# MIXR_Power_-_Battery_Management_System.net
KiCad netlist of a schematic drawn in Altium Designer
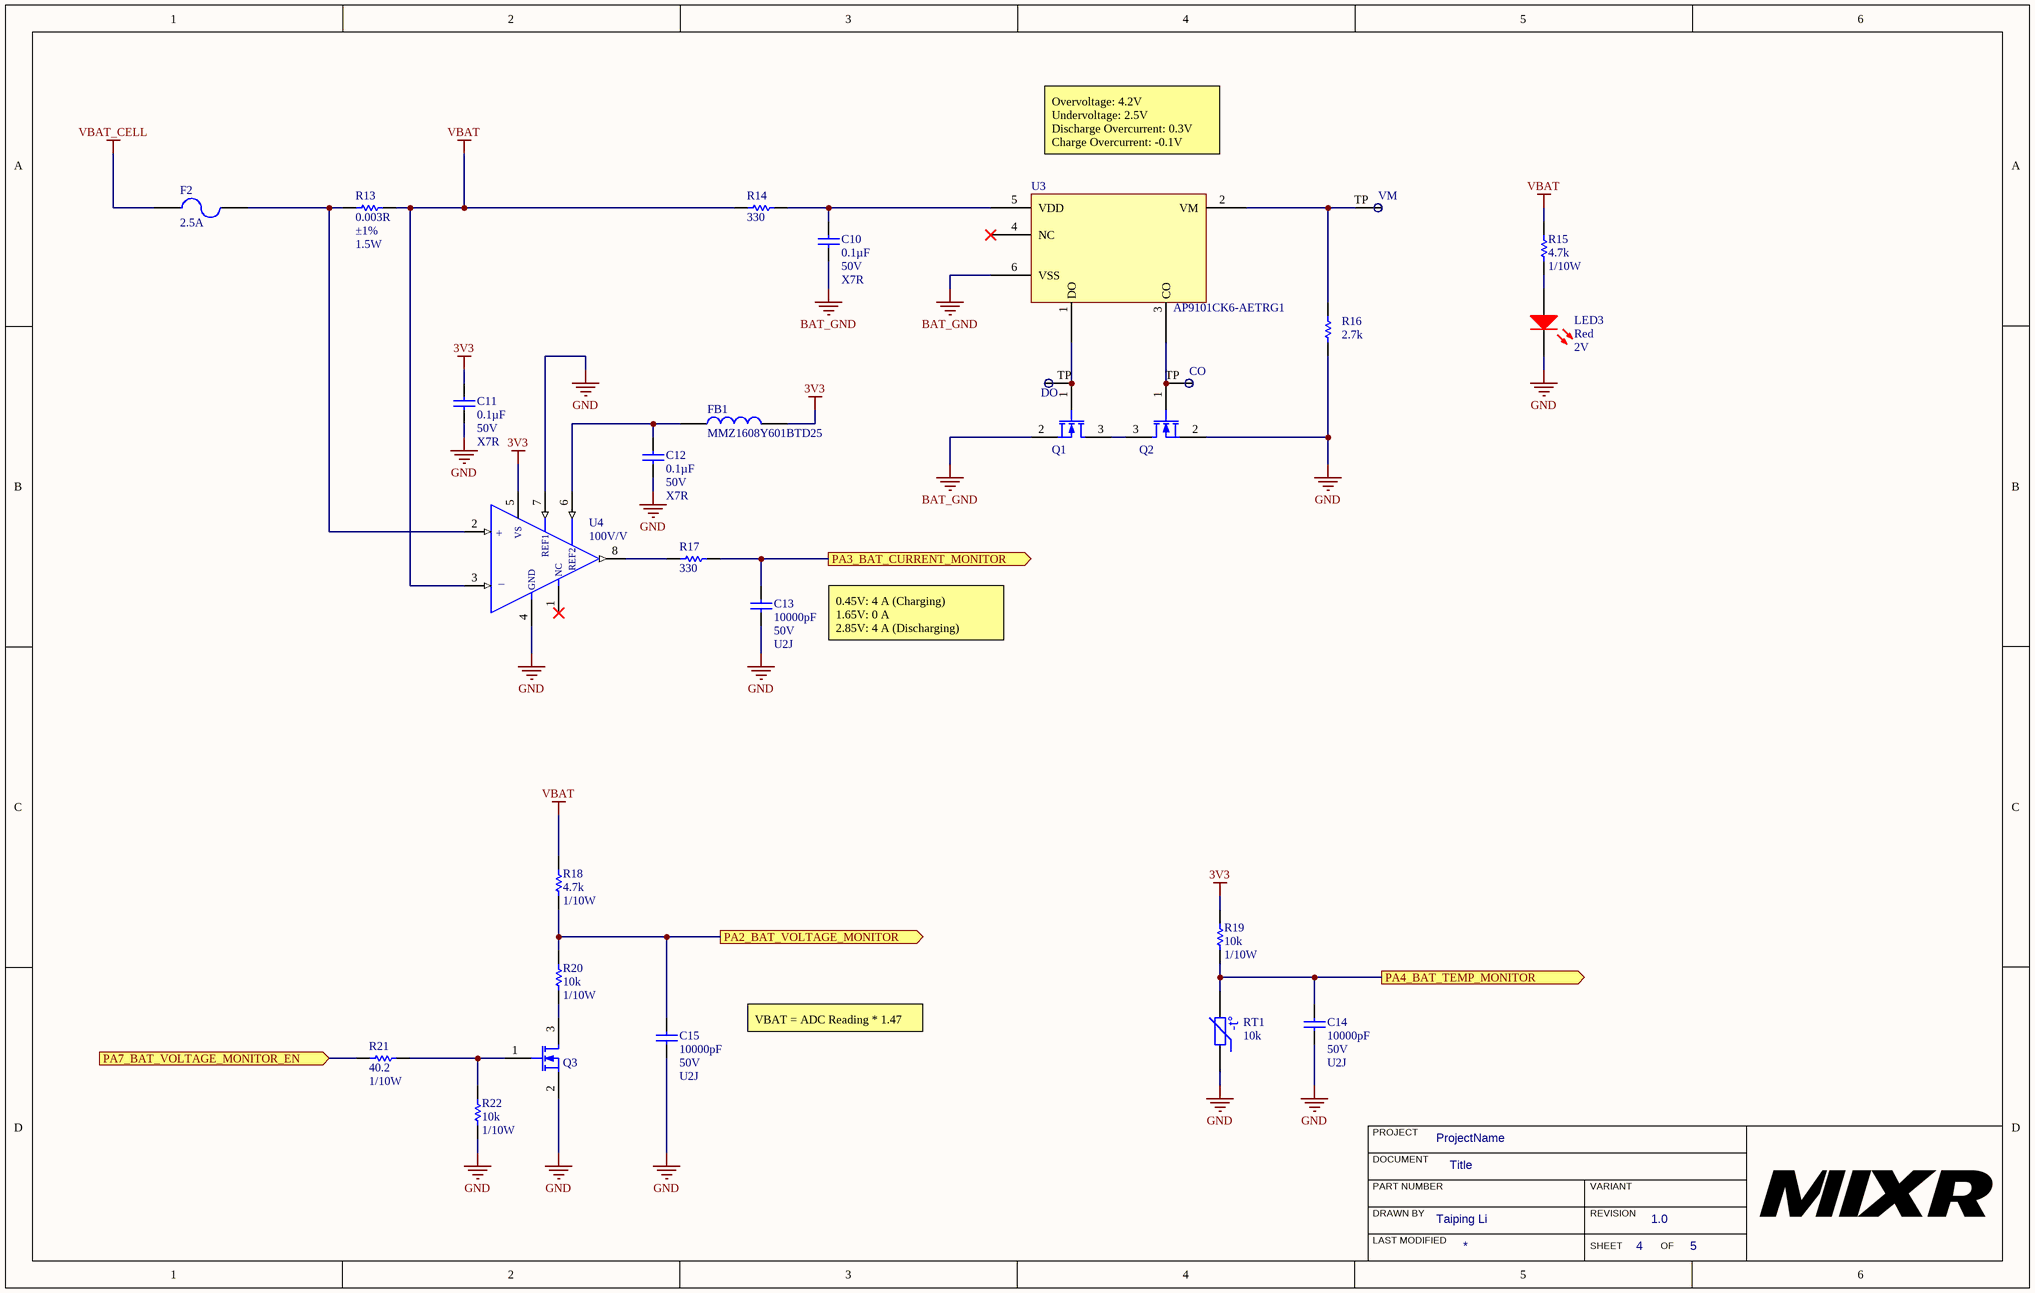
[diagram p0: MIXR Power - Battery Management System.SchDoc]

(export (version "E")
  (design (tool "Eeschema 10.0.6"))
  (components
    (comp (ref "C10")
      (value "CAP CER 0.1UF 50V 10% X7R 0603")
      (footprint "CAP, 0603")
      (description "0.10µF ±10% 50V Ceramic Capacitor X7R 0603 (1608 Metric)")
      (fields
        (field (name "TOLERANCE") "±10%")
        (field (name "CAPACITANCE") "0.1µF")
        (field (name "VOLTAGE") "50V")
        (field (name "TEMPERATURE COEFFICIENT") "X7R")
      )
      (libsource (lib "Schematic Diagrams") (part "CAP CER 0.1UF 50V 10% X7R 0603"))
    )
    (comp (ref "C11")
      (value "CAP CER 0.1UF 50V 10% X7R 0603")
      (footprint "CAP, 0603")
      (description "0.10µF ±10% 50V Ceramic Capacitor X7R 0603 (1608 Metric)")
      (fields
        (field (name "TOLERANCE") "±10%")
        (field (name "CAPACITANCE") "0.1µF")
        (field (name "VOLTAGE") "50V")
        (field (name "TEMPERATURE COEFFICIENT") "X7R")
      )
      (libsource (lib "Schematic Diagrams") (part "CAP CER 0.1UF 50V 10% X7R 0603"))
    )
    (comp (ref "C12")
      (value "CAP CER 0.1UF 50V 10% X7R 0603")
      (footprint "CAP, 0603")
      (description "0.10µF ±10% 50V Ceramic Capacitor X7R 0603 (1608 Metric)")
      (fields
        (field (name "TOLERANCE") "±10%")
        (field (name "CAPACITANCE") "0.1µF")
        (field (name "VOLTAGE") "50V")
        (field (name "TEMPERATURE COEFFICIENT") "X7R")
      )
      (libsource (lib "Schematic Diagrams") (part "CAP CER 0.1UF 50V 10% X7R 0603"))
    )
    (comp (ref "C13")
      (value "CAP CER 10nF 50V 5% X7R 0603")
      (footprint "CAP, 0603")
      (description "10000pF ±5% 50V Ceramic Capacitor U2J 0603 (1608 Metric)")
      (fields
        (field (name "TOLERANCE") "±5%")
        (field (name "CAPACITANCE") "10000pF")
        (field (name "VOLTAGE") "50V")
        (field (name "TEMPERATURE COEFFICIENT") "U2J")
      )
      (libsource (lib "Schematic Diagrams") (part "CAP CER 10nF 50V 5% X7R 0603"))
    )
    (comp (ref "C14")
      (value "CAP CER 10nF 50V 5% X7R 0603")
      (footprint "CAP, 0603")
      (description "10000pF ±5% 50V Ceramic Capacitor U2J 0603 (1608 Metric)")
      (fields
        (field (name "TOLERANCE") "±5%")
        (field (name "CAPACITANCE") "10000pF")
        (field (name "VOLTAGE") "50V")
        (field (name "TEMPERATURE COEFFICIENT") "U2J")
      )
      (libsource (lib "Schematic Diagrams") (part "CAP CER 10nF 50V 5% X7R 0603"))
    )
    (comp (ref "C15")
      (value "CAP CER 10nF 50V 5% X7R 0603")
      (footprint "CAP, 0603")
      (description "10000pF ±5% 50V Ceramic Capacitor U2J 0603 (1608 Metric)")
      (fields
        (field (name "TOLERANCE") "±5%")
        (field (name "CAPACITANCE") "10000pF")
        (field (name "VOLTAGE") "50V")
        (field (name "TEMPERATURE COEFFICIENT") "U2J")
      )
      (libsource (lib "Schematic Diagrams") (part "CAP CER 10nF 50V 5% X7R 0603"))
    )
    (comp (ref "CO")
      (value "Test Point")
      (footprint "Test Point")
      (libsource (lib "Schematic Diagrams") (part "Test Point"))
    )
    (comp (ref "DO")
      (value "Test Point")
      (footprint "Test Point")
      (libsource (lib "Schematic Diagrams") (part "Test Point"))
    )
    (comp (ref "F2")
      (value "FUSE 2.5A 32VDC 1206")
      (footprint "FUSE LITTLEFUSE 0466 1206")
      (description "2.5A 32V AC 32V DC Fuse Board Mount (Cartridge Style Excluded) Surface Mount 1206 (3216 Metric)")
      (fields (field (name "CURRENT RATING") "2.5A"))
      (libsource (lib "Schematic Diagrams") (part "FUSE 2.5A 32VDC 1206"))
    )
    (comp (ref "FB1")
      (value "FB 600 OHM 1LN 0603")
      (footprint "FB 0603")
      (description "FERRITE BEAD 600 OHM 0603 1LN")
      (fields
        (field (name "MANUFACTURER") "TDK")
        (field (name "TOLERANCE") "25%")
        (field (name "MANUFACTURER PART NUMBER") "MMZ1608Y601BTD25")
      )
      (libsource (lib "Schematic Diagrams") (part "FB 600 OHM 1LN 0603"))
    )
    (comp (ref "LED3")
      (value "LED RED CLEAR 2V 0603")
      (footprint "LED_0603")
      (description "Red 631nm LED Indication - Discrete 2V 0603 (1608 Metric)")
      (fields
        (field (name "MANUFACTURER") "Wurth Electronics Inc.")
        (field (name "MANUFACTURER PART NUMBER") "150060RS75000")
        (field (name "COLOR") "Red")
        (field (name "VOLTAGE - FORWARD (VF) (TYP)") "2V")
      )
      (libsource (lib "Schematic Diagrams") (part "LED RED CLEAR 2V 0603"))
    )
    (comp (ref "Q1")
      (value "MOSFET N-CH 30V 6.2A 0.9W SOT-23")
      (footprint "MOSFET N-CH 30V 6.2A 0.9W SOT-23")
      (description "N-Channel 30V 6.2A (Ta) 900mW (Ta) Surface Mount SOT-23")
      (fields (field (name "MANUFACTURER") "Diodes") (field (name "MANUFACTURER PART NUMBER") "DMN3023L-7"))
      (libsource (lib "Schematic Diagrams") (part "MOSFET N-CH 30V 6.2A 0.9W SOT-23"))
    )
    (comp (ref "Q2")
      (value "MOSFET N-CH 30V 6.2A 0.9W SOT-23")
      (footprint "MOSFET N-CH 30V 6.2A 0.9W SOT-23")
      (description "N-Channel 30V 6.2A (Ta) 900mW (Ta) Surface Mount SOT-23")
      (fields (field (name "MANUFACTURER") "Diodes") (field (name "MANUFACTURER PART NUMBER") "DMN3023L-7"))
      (libsource (lib "Schematic Diagrams") (part "MOSFET N-CH 30V 6.2A 0.9W SOT-23"))
    )
    (comp (ref "Q3")
      (value "MOSFET N-CH 30V 6.2A 0.9W SOT-23")
      (footprint "MOSFET N-CH 30V 6.2A 0.9W SOT-23")
      (description "N-Channel 30V 6.2A (Ta) 900mW (Ta) Surface Mount SOT-23")
      (fields (field (name "MANUFACTURER") "Diodes") (field (name "MANUFACTURER PART NUMBER") "DMN3023L-7"))
      (libsource (lib "Schematic Diagrams") (part "MOSFET N-CH 30V 6.2A 0.9W SOT-23"))
    )
    (comp (ref "R13")
      (value "RES 0.003 OHM 1% 1.5W 2010")
      (footprint "RES 2010")
      (description "0.003 Ohm ±1% 1.5W Chip Resistor 2010 (5025 Metric) Current Sense, Moisture Resistant Metal Foil")
      (fields
        (field (name "RESISTANCE (OHMS)") "0.003R")
        (field (name "TOLERANCE") "±1%")
        (field (name "POWER (WATTS)") "1.5W")
      )
      (libsource (lib "Schematic Diagrams") (part "RES 0.003 OHM 1% 1.5W 2010"))
    )
    (comp (ref "R14")
      (value "330")
      (footprint "RES, 0603")
      (fields
        (field (name "MANUFACTURER") "TE Connectivity")
        (field (name "MANUFACTURER PART NUMBER") "CRGCQ0603F330R")
        (field (name "Comment") "RES 330 OHM 1% 1/10W 0603")
      )
      (libsource (lib "Schematic Diagrams") (part "RES 330 OHM 1% 1/10W 0603"))
    )
    (comp (ref "R15")
      (value "RES 4.7K OHM 1% 1/10W 0603")
      (footprint "RES, 0603")
      (description "4.7k Ohm ±1% 0.1W, 1/10W Chip Resistor 0603 (1608 Metric) Moisture Resistant Thick Film")
      (fields
        (field (name "TOLERANCE") "±1%")
        (field (name "RESISTANCE (OHMS)") "4.7k")
        (field (name "POWER (WATTS)") "1/10W")
      )
      (libsource (lib "Schematic Diagrams") (part "RES 4.7K OHM 1% 1/10W 0603"))
    )
    (comp (ref "R16")
      (value "2.7k")
      (footprint "RES, 0603")
      (fields
        (field (name "MANUFACTURER") "TE Connectivity")
        (field (name "MANUFACTURER PART NUMBER") "CRGCQ0603F2K7")
      )
      (libsource (lib "Schematic Diagrams") (part "RES 2.7K OHM 1% 1/10W 0603"))
    )
    (comp (ref "R17")
      (value "330")
      (footprint "RES, 0603")
      (fields
        (field (name "MANUFACTURER") "TE Connectivity")
        (field (name "MANUFACTURER PART NUMBER") "CRGCQ0603F330R")
        (field (name "Comment") "RES 330 OHM 1% 1/10W 0603")
      )
      (libsource (lib "Schematic Diagrams") (part "RES 330 OHM 1% 1/10W 0603"))
    )
    (comp (ref "R18")
      (value "RES 4.7K OHM 1% 1/10W 0603")
      (footprint "RES, 0603")
      (description "4.7k Ohm ±1% 0.1W, 1/10W Chip Resistor 0603 (1608 Metric) Moisture Resistant Thick Film")
      (fields
        (field (name "TOLERANCE") "±1%")
        (field (name "RESISTANCE (OHMS)") "4.7k")
        (field (name "POWER (WATTS)") "1/10W")
      )
      (libsource (lib "Schematic Diagrams") (part "RES 4.7K OHM 1% 1/10W 0603"))
    )
    (comp (ref "R19")
      (value "RES 10K OHM 1% 1/10W 0603")
      (footprint "RES, 0603")
      (description "RES SMD 10K OHM 1% 1/10W 0603")
      (fields
        (field (name "TOLERANCE") "±1%")
        (field (name "RESISTANCE") "10k")
        (field (name "POWER") "1/10W")
      )
      (libsource (lib "Schematic Diagrams") (part "RES 10K OHM 1% 1/10W 0603"))
    )
    (comp (ref "R20")
      (value "RES 10K OHM 1% 1/10W 0603")
      (footprint "RES, 0603")
      (description "RES SMD 10K OHM 1% 1/10W 0603")
      (fields
        (field (name "TOLERANCE") "±1%")
        (field (name "RESISTANCE") "10k")
        (field (name "POWER") "1/10W")
      )
      (libsource (lib "Schematic Diagrams") (part "RES 10K OHM 1% 1/10W 0603"))
    )
    (comp (ref "R21")
      (value "RES 40.2 OHM 0.5% 1/10W 0603")
      (footprint "RES, 0603")
      (description "RES SMD 40.2 OHM 0.5% 1/10W 0603")
      (fields
        (field (name "TOLERANCE") "±0.5%")
        (field (name "RESISTANCE") "40.2")
        (field (name "POWER") "1/10W")
      )
      (libsource (lib "Schematic Diagrams") (part "RES 40.2 OHM 0.5% 1/10W 0603"))
    )
    (comp (ref "R22")
      (value "RES 10K OHM 1% 1/10W 0603")
      (footprint "RES, 0603")
      (description "RES SMD 10K OHM 1% 1/10W 0603")
      (fields
        (field (name "TOLERANCE") "±1%")
        (field (name "RESISTANCE") "10k")
        (field (name "POWER") "1/10W")
      )
      (libsource (lib "Schematic Diagrams") (part "RES 10K OHM 1% 1/10W 0603"))
    )
    (comp (ref "RT1")
      (value "NTC THERMISTORS 10K 0603 SMD")
      (footprint "RES, 0603")
      (description "NTC THERMISTORS 10KOHM 1608 SMD")
      (fields
        (field (name "MANUFACTURER") "Murata Electronics North America")
        (field (name "MANUFACTURER PART NUMBER") "NCU18XH103F60RB")
        (field (name "RESISTANCE IN OHMS @ 25°C") "10k")
      )
      (libsource (lib "Schematic Diagrams") (part "NTC THERMISTORS 10K 0603 SMD"))
    )
    (comp (ref "U3")
      (value "IC BATT PROT LI-ION 1-CELL SOT26")
      (footprint "SOT23-6")
      (description "Battery Battery Protection IC Lithium Ion/Polymer SOT-26")
      (fields
        (field (name "MANUFACTURER") "Diodes")
        (field (name "MANUFACTURER PART NUMBER") "AP9101CK6-AETRG1")
      )
      (libsource (lib "Schematic Diagrams") (part "IC BATT PROT LI-ION 1-CELL SOT26"))
    )
    (comp (ref "U4")
      (value "100V/V")
      (footprint "IC CURRENT AMPLIFIER INA240 TSSOP-8")
      (description "Current Sense Amplifier 1 Circuit 8-TSSOP")
      (libsource (lib "Schematic Diagrams") (part "IC CURRENT AMPLIFIER INA240 8-TSSOP"))
    )
    (comp (ref "VM")
      (value "Test Point")
      (footprint "Test Point")
      (libsource (lib "Schematic Diagrams") (part "Test Point"))
    )
  )
  (nets
    (net (code "1") (name "/PA2_BAT_VOLTAGE_MONITOR") (class "Default")
      (node (ref "C15") (pin "1") (pinfunction "1_1") (pintype "passive"))
      (node (ref "R18") (pin "2") (pinfunction "2_2") (pintype "passive"))
      (node (ref "R20") (pin "1") (pinfunction "1_1") (pintype "passive"))
    )
    (net (code "2") (name "/PA3_BAT_CURRENT_MONITOR") (class "Default")
      (node (ref "C13") (pin "1") (pinfunction "1_1") (pintype "passive"))
      (node (ref "R17") (pin "2") (pinfunction "2_2") (pintype "passive"))
    )
    (net (code "3") (name "/PA4_BAT_TEMP_MONITOR") (class "Default")
      (node (ref "C14") (pin "1") (pinfunction "1_1") (pintype "passive"))
      (node (ref "R19") (pin "2") (pinfunction "2_2") (pintype "passive"))
      (node (ref "RT1") (pin "2") (pinfunction "2_2") (pintype "passive"))
    )
    (net (code "4") (name "/PA7_BAT_VOLTAGE_MONITOR_EN") (class "Default")
      (node (ref "R21") (pin "1") (pinfunction "1_1") (pintype "passive"))
    )
    (net (code "5") (name "3V3") (class "Default")
      (node (ref "C11") (pin "1") (pinfunction "1_1") (pintype "passive"))
      (node (ref "FB1") (pin "2") (pinfunction "2_2") (pintype "passive"))
      (node (ref "R19") (pin "1") (pinfunction "1_1") (pintype "passive"))
      (node (ref "U4") (pin "5") (pinfunction "VS_5") (pintype "power_in"))
    )
    (net (code "6") (name "BAT_GND") (class "Default")
      (node (ref "C10") (pin "2") (pinfunction "2_2") (pintype "passive"))
      (node (ref "Q1") (pin "2") (pinfunction "S_2") (pintype "passive"))
      (node (ref "U3") (pin "6") (pinfunction "VSS_6") (pintype "passive"))
    )
    (net (code "7") (name "GND") (class "Default")
      (node (ref "C11") (pin "2") (pinfunction "2_2") (pintype "passive"))
      (node (ref "C12") (pin "2") (pinfunction "2_2") (pintype "passive"))
      (node (ref "C13") (pin "2") (pinfunction "2_2") (pintype "passive"))
      (node (ref "C14") (pin "2") (pinfunction "2_2") (pintype "passive"))
      (node (ref "C15") (pin "2") (pinfunction "2_2") (pintype "passive"))
      (node (ref "LED3") (pin "2") (pinfunction "K_2") (pintype "passive"))
      (node (ref "Q2") (pin "2") (pinfunction "S_2") (pintype "passive"))
      (node (ref "Q3") (pin "2") (pinfunction "S_2") (pintype "passive"))
      (node (ref "R16") (pin "2") (pinfunction "2_2") (pintype "passive"))
      (node (ref "R22") (pin "2") (pinfunction "2_2") (pintype "passive"))
      (node (ref "RT1") (pin "1") (pinfunction "1_1") (pintype "passive"))
      (node (ref "U4") (pin "4") (pinfunction "GND_4") (pintype "power_in"))
      (node (ref "U4") (pin "7") (pinfunction "REF1_7") (pintype "input"))
    )
    (net (code "8") (name "Net-(CO-1)") (class "Default")
      (node (ref "CO") (pin "TP") (pinfunction "1_TP") (pintype "passive"))
      (node (ref "Q2") (pin "1") (pinfunction "G_1") (pintype "passive"))
      (node (ref "U3") (pin "3") (pinfunction "CO_3") (pintype "passive"))
    )
    (net (code "9") (name "Net-(DO-1)") (class "Default")
      (node (ref "DO") (pin "TP") (pinfunction "1_TP") (pintype "passive"))
      (node (ref "Q1") (pin "1") (pinfunction "G_1") (pintype "passive"))
      (node (ref "U3") (pin "1") (pinfunction "DO_1") (pintype "passive"))
    )
    (net (code "10") (name "Net-(LED3-A)") (class "Default")
      (node (ref "LED3") (pin "1") (pinfunction "A_1") (pintype "passive"))
      (node (ref "R15") (pin "2") (pinfunction "2_2") (pintype "passive"))
    )
    (net (code "11") (name "Net-(Q1-D)") (class "Default")
      (node (ref "Q1") (pin "3") (pinfunction "D_3") (pintype "passive"))
      (node (ref "Q2") (pin "3") (pinfunction "D_3") (pintype "passive"))
    )
    (net (code "12") (name "Net-(Q3-D)") (class "Default")
      (node (ref "Q3") (pin "3") (pinfunction "D_3") (pintype "passive"))
      (node (ref "R20") (pin "2") (pinfunction "2_2") (pintype "passive"))
    )
    (net (code "13") (name "Net-(Q3-G)") (class "Default")
      (node (ref "Q3") (pin "1") (pinfunction "G_1") (pintype "passive"))
      (node (ref "R21") (pin "2") (pinfunction "2_2") (pintype "passive"))
      (node (ref "R22") (pin "1") (pinfunction "1_1") (pintype "passive"))
    )
    (net (code "14") (name "Net-(U3-VDD)") (class "Default")
      (node (ref "C10") (pin "1") (pinfunction "1_1") (pintype "passive"))
      (node (ref "R14") (pin "2") (pinfunction "2_2") (pintype "passive"))
      (node (ref "U3") (pin "5") (pinfunction "VDD_5") (pintype "passive"))
    )
    (net (code "15") (name "Net-(U3-VM)") (class "Default")
      (node (ref "R16") (pin "1") (pinfunction "1_1") (pintype "passive"))
      (node (ref "U3") (pin "2") (pinfunction "VM_2") (pintype "passive"))
      (node (ref "VM") (pin "TP") (pinfunction "1_TP") (pintype "passive"))
    )
    (net (code "16") (name "Net-(U4-+IN)") (class "Default")
      (node (ref "F2") (pin "2") (pinfunction "2_2") (pintype "passive"))
      (node (ref "R13") (pin "1") (pinfunction "1_1") (pintype "passive"))
      (node (ref "U4") (pin "2") (pinfunction "+IN_2") (pintype "input"))
    )
    (net (code "17") (name "Net-(U4-OUTPUT)") (class "Default")
      (node (ref "R17") (pin "1") (pinfunction "1_1") (pintype "passive"))
      (node (ref "U4") (pin "8") (pinfunction "OUTPUT_8") (pintype "output"))
    )
    (net (code "18") (name "Net-(U4-REF2)") (class "Default")
      (node (ref "C12") (pin "1") (pinfunction "1_1") (pintype "passive"))
      (node (ref "FB1") (pin "1") (pinfunction "1_1") (pintype "passive"))
      (node (ref "U4") (pin "6") (pinfunction "REF2_6") (pintype "input"))
    )
    (net (code "19") (name "VBAT") (class "Default")
      (node (ref "R13") (pin "2") (pinfunction "2_2") (pintype "passive"))
      (node (ref "R14") (pin "1") (pinfunction "1_1") (pintype "passive"))
      (node (ref "R15") (pin "1") (pinfunction "1_1") (pintype "passive"))
      (node (ref "R18") (pin "1") (pinfunction "1_1") (pintype "passive"))
      (node (ref "U4") (pin "3") (pinfunction "-IN_3") (pintype "input"))
    )
    (net (code "20") (name "VBAT_CELL") (class "Default")
      (node (ref "F2") (pin "1") (pinfunction "1_1") (pintype "passive"))
    )
    (net (code "21") (name "unconnected-(U3-NC-Pad4)") (class "Default")
      (node (ref "U3") (pin "4") (pinfunction "NC_4") (pintype "passive+no_connect"))
    )
    (net (code "22") (name "unconnected-(U4-NC-Pad1)") (class "Default")
      (node (ref "U4") (pin "1") (pinfunction "NC_1") (pintype "power_in+no_connect"))
    )
  )
)
